# interface.net
KiCad netlist of a schematic drawn in Altium Designer
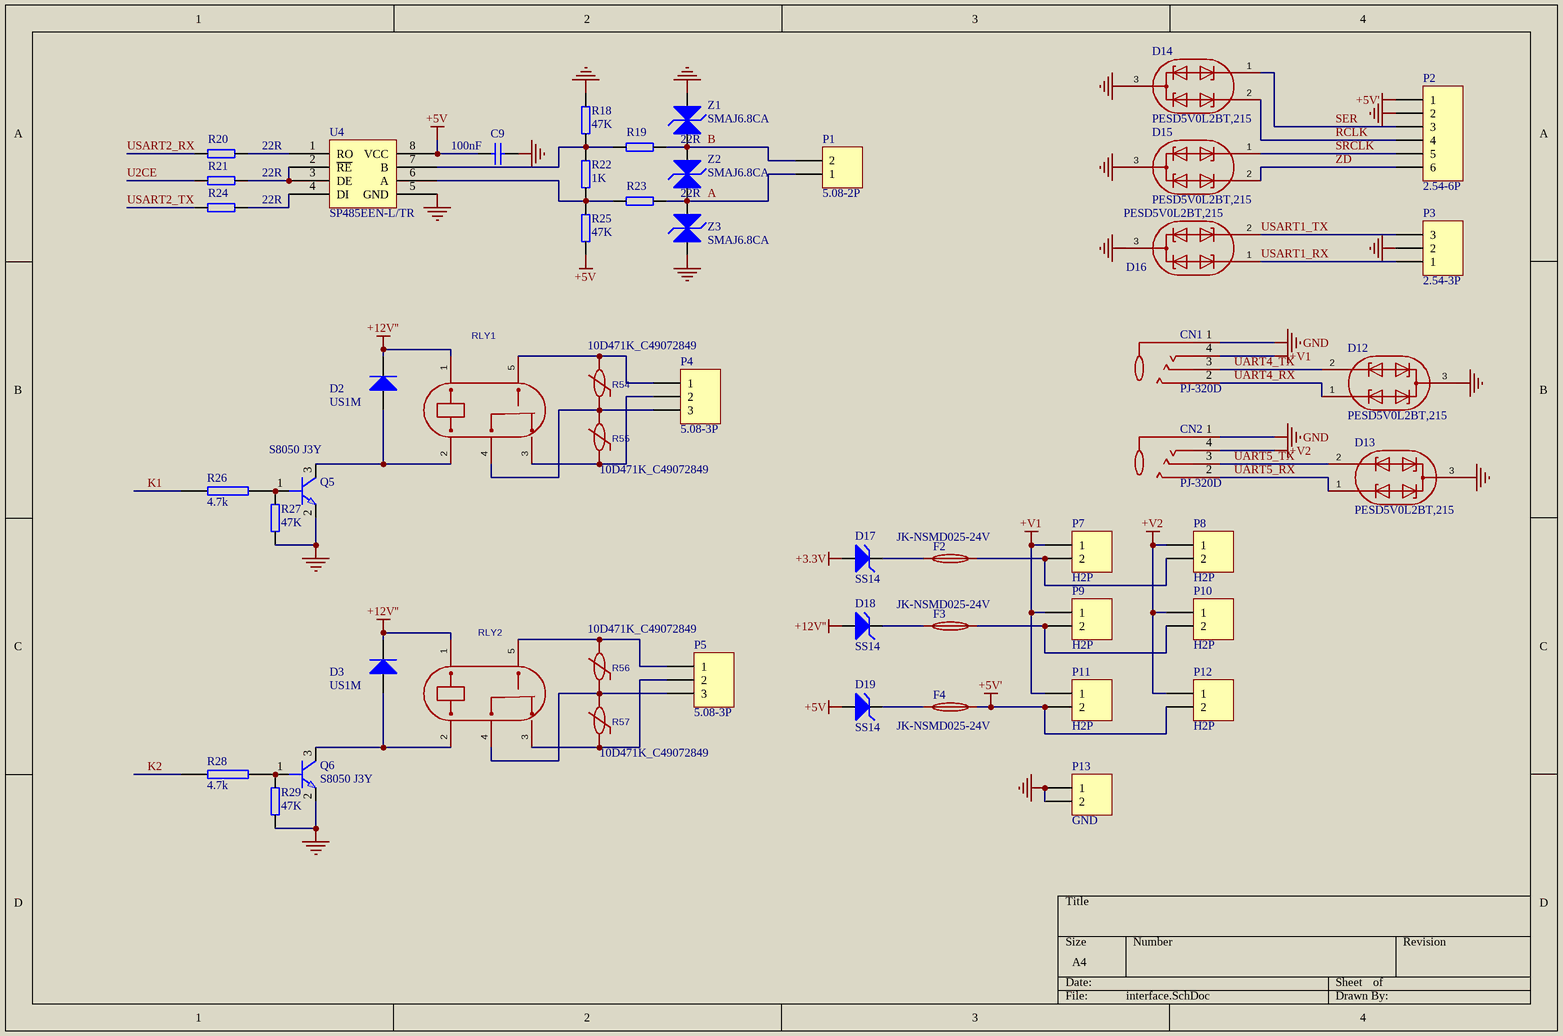
[diagram p0: interface.SchDoc]

(export (version "E")
  (design (tool "Eeschema 10.0.6"))
  (components
    (comp (ref "C9")
      (value "100nF")
      (footprint "LC-0805_C")
      (description "Capacitor")
      (fields (field (name "PUBLISHER") "Altium Limited"))
      (libsource (lib "*") (part "CAP"))
    )
    (comp (ref "CN1")
      (value "PJ-320D")
      (footprint "4PIN")
      (fields (field (name "MANUFACTURER") "SHOU HAN(首韩)"))
      (libsource (lib "altium-import") (part "root_0_PJ-320D_C431535_"))
    )
    (comp (ref "CN2")
      (value "PJ-320D")
      (footprint "4PIN")
      (fields (field (name "MANUFACTURER") "SHOU HAN(首韩)"))
      (libsource (lib "altium-import") (part "root_0_PJ-320D_C431535_"))
    )
    (comp (ref "D2")
      (value "US1M")
      (footprint "LC-SMA(DO-214AC)_S2")
      (description "Default Diode")
      (fields (field (name "PUBLISHER") "Altium Limited"))
      (libsource (lib "Miscellaneous Devices") (part "Diode"))
    )
    (comp (ref "D3")
      (value "US1M")
      (footprint "LC-SMA(DO-214AC)_S2")
      (description "Default Diode")
      (fields (field (name "PUBLISHER") "Altium Limited"))
      (libsource (lib "Miscellaneous Devices") (part "Diode"))
    )
    (comp (ref "D12")
      (value "PESD5V0L2BT,215")
      (footprint "SOT-23")
      (libsource (lib "altium-import") (part "root_2_mirrored_PESD5V0L2BT,215_"))
    )
    (comp (ref "D13")
      (value "PESD5V0L2BT,215")
      (footprint "SOT-23")
      (libsource (lib "altium-import") (part "root_2_mirrored_PESD5V0L2BT,215_"))
    )
    (comp (ref "D14")
      (value "PESD5V0L2BT,215")
      (footprint "SOT-23")
      (libsource (lib "altium-import") (part "root_0_mirrored_PESD5V0L2BT,215_"))
    )
    (comp (ref "D15")
      (value "PESD5V0L2BT,215")
      (footprint "SOT-23")
      (libsource (lib "altium-import") (part "root_0_mirrored_PESD5V0L2BT,215_"))
    )
    (comp (ref "D16")
      (value "PESD5V0L2BT,215")
      (footprint "SOT-23")
      (libsource (lib "altium-import") (part "root_2_PESD5V0L2BT,215_"))
    )
    (comp (ref "D17")
      (value "SS14")
      (footprint "LC-SMA(DO-214AC)_S5")
      (description "constant diode")
      (libsource (lib "*") (part "CONSTANT"))
    )
    (comp (ref "D18")
      (value "SS14")
      (footprint "LC-SMA(DO-214AC)_S5")
      (description "constant diode")
      (libsource (lib "*") (part "CONSTANT"))
    )
    (comp (ref "D19")
      (value "SS14")
      (footprint "LC-SMA(DO-214AC)_S5")
      (description "constant diode")
      (libsource (lib "*") (part "CONSTANT"))
    )
    (comp (ref "F2")
      (value "JK-NSMD025-24V")
      (footprint "LC-1206_R")
      (fields (field (name "MANUFACTURER") "JK(金科)") (field (name "MANUFACTURER PART") "JK-MSMD110-24V"))
      (libsource (lib "altium-import") (part "root_0_JK-MSMD110-24V_"))
    )
    (comp (ref "F3")
      (value "JK-NSMD025-24V")
      (footprint "LC-1206_R")
      (fields (field (name "MANUFACTURER") "JK(金科)") (field (name "MANUFACTURER PART") "JK-MSMD110-24V"))
      (libsource (lib "altium-import") (part "root_0_JK-MSMD110-24V_"))
    )
    (comp (ref "F4")
      (value "JK-NSMD025-24V")
      (footprint "LC-1206_R")
      (fields (field (name "MANUFACTURER") "JK(金科)") (field (name "MANUFACTURER PART") "JK-MSMD110-24V"))
      (libsource (lib "altium-import") (part "root_0_JK-MSMD110-24V_"))
    )
    (comp (ref "P1")
      (value "5.08-2P")
      (footprint "MKDSN_2RMI")
      (description "Header, 2-Pin")
      (fields (field (name "PUBLISHER") "Altium Limited"))
      (libsource (lib "") (part "Header 2_1"))
    )
    (comp (ref "P2")
      (value "2.54-6P")
      (footprint "6PIN")
      (description "Header, 6-Pin")
      (fields (field (name "PUBLISHER") "Altium Limited"))
      (libsource (lib "Miscellaneous Connectors") (part "Header 6"))
    )
    (comp (ref "P3")
      (value "2.54-3P")
      (footprint "3PIN")
      (description "Header, 3-Pin")
      (fields (field (name "PUBLISHER") "Altium Limited"))
      (libsource (lib "") (part "Header 3_1"))
    )
    (comp (ref "P4")
      (value "5.08-3P")
      (footprint "5.08-3P")
      (description "Header, 3-Pin")
      (fields (field (name "PUBLISHER") "Altium Limited"))
      (libsource (lib "Miscellaneous Connectors") (part "Header 3"))
    )
    (comp (ref "P5")
      (value "5.08-3P")
      (footprint "5.08-3P")
      (description "Header, 3-Pin")
      (fields (field (name "PUBLISHER") "Altium Limited"))
      (libsource (lib "Miscellaneous Connectors") (part "Header 3"))
    )
    (comp (ref "P7")
      (value "H2P")
      (footprint "HDR1X2")
      (description "Header, 2-Pin")
      (fields (field (name "PUBLISHER") "Altium Limited"))
      (libsource (lib "Miscellaneous Connectors") (part "Header 2"))
    )
    (comp (ref "P8")
      (value "H2P")
      (footprint "HDR1X2")
      (description "Header, 2-Pin")
      (fields (field (name "PUBLISHER") "Altium Limited"))
      (libsource (lib "Miscellaneous Connectors") (part "Header 2"))
    )
    (comp (ref "P9")
      (value "H2P")
      (footprint "HDR1X2")
      (description "Header, 2-Pin")
      (fields (field (name "PUBLISHER") "Altium Limited"))
      (libsource (lib "Miscellaneous Connectors") (part "Header 2"))
    )
    (comp (ref "P10")
      (value "H2P")
      (footprint "HDR1X2")
      (description "Header, 2-Pin")
      (fields (field (name "PUBLISHER") "Altium Limited"))
      (libsource (lib "Miscellaneous Connectors") (part "Header 2"))
    )
    (comp (ref "P11")
      (value "H2P")
      (footprint "HDR1X2")
      (description "Header, 2-Pin")
      (fields (field (name "PUBLISHER") "Altium Limited"))
      (libsource (lib "Miscellaneous Connectors") (part "Header 2"))
    )
    (comp (ref "P12")
      (value "H2P")
      (footprint "HDR1X2")
      (description "Header, 2-Pin")
      (fields (field (name "PUBLISHER") "Altium Limited"))
      (libsource (lib "Miscellaneous Connectors") (part "Header 2"))
    )
    (comp (ref "P13")
      (value "GND")
      (footprint "HDR1X2")
      (description "Header, 2-Pin")
      (fields (field (name "PUBLISHER") "Altium Limited"))
      (libsource (lib "Miscellaneous Connectors") (part "Header 2"))
    )
    (comp (ref "Q5") (value "S8050 J3Y") (footprint "SOT-23") (libsource (lib "*") (part "2N5551")))
    (comp (ref "Q6") (value "S8050 J3Y") (footprint "SOT-23") (libsource (lib "*") (part "2N5551")))
    (comp (ref "R18")
      (value "47K")
      (footprint "LC-0805_R")
      (description "1K")
      (libsource (lib "*") (part "RES22"))
    )
    (comp (ref "R19") (value "22R") (footprint "LC-0805_R") (libsource (lib "*") (part "RES22")))
    (comp (ref "R20")
      (value "22R")
      (footprint "LC-0805_R")
      (description "1K")
      (libsource (lib "*") (part "RES22"))
    )
    (comp (ref "R21")
      (value "22R")
      (footprint "LC-0805_R")
      (description "1K")
      (libsource (lib "*") (part "RES22"))
    )
    (comp (ref "R22") (value "1K") (footprint "LC-0805_R") (libsource (lib "*") (part "RES22")))
    (comp (ref "R23")
      (value "22R")
      (footprint "LC-0805_R")
      (description "1K")
      (libsource (lib "*") (part "RES22"))
    )
    (comp (ref "R24")
      (value "22R")
      (footprint "LC-0805_R")
      (description "1K")
      (libsource (lib "*") (part "RES22"))
    )
    (comp (ref "R25")
      (value "47K")
      (footprint "LC-0805_R")
      (description "1K")
      (libsource (lib "*") (part "RES22"))
    )
    (comp (ref "R26") (value "4.7k") (footprint "LC-0805_R") (libsource (lib "*") (part "RES2")))
    (comp (ref "R27")
      (value "47K")
      (footprint "LC-0805_R")
      (description "1K")
      (libsource (lib "*") (part "RES22"))
    )
    (comp (ref "R28") (value "4.7k") (footprint "LC-0805_R") (libsource (lib "*") (part "RES2")))
    (comp (ref "R29")
      (value "47K")
      (footprint "LC-0805_R")
      (description "1K")
      (libsource (lib "*") (part "RES22"))
    )
    (comp (ref "R54")
      (value "10D471K_C49072849")
      (footprint "RES-TH_L11.0-W6.0-P7.50")
      (libsource (lib "altium-import") (part "root_1_14D471K_C49069733_"))
    )
    (comp (ref "R55")
      (value "10D471K_C49072849")
      (footprint "RES-TH_L11.0-W6.0-P7.50")
      (libsource (lib "altium-import") (part "root_1_14D471K_C49069733_"))
    )
    (comp (ref "R56")
      (value "10D471K_C49072849")
      (footprint "RES-TH_L11.0-W6.0-P7.50")
      (libsource (lib "altium-import") (part "root_1_14D471K_C49069733_"))
    )
    (comp (ref "R57")
      (value "10D471K_C49072849")
      (footprint "RES-TH_L11.0-W6.0-P7.50")
      (libsource (lib "altium-import") (part "root_1_14D471K_C49069733_"))
    )
    (comp (ref "RLY1")
      (value "JQC-3FF/12VDC-1ZS(551)")
      (libsource (lib "altium-import") (part "root_0_JQC-3FF/12VDC-1ZS(551)_"))
    )
    (comp (ref "RLY2")
      (value "JQC-3FF/12VDC-1ZS(551)")
      (libsource (lib "altium-import") (part "root_0_JQC-3FF/12VDC-1ZS(551)_"))
    )
    (comp (ref "U4")
      (value "SP485EEN-L/TR")
      (footprint "LC-SOIC-8_150mil")
      (libsource (lib "*") (part "MAX483"))
    )
    (comp (ref "Z1")
      (value "SMAJ6.8CA")
      (footprint "1812")
      (description "DIODE BRIDGE")
      (libsource (lib "*") (part "BANQIAO"))
    )
    (comp (ref "Z2")
      (value "SMAJ6.8CA")
      (footprint "1812")
      (description "DIODE BRIDGE")
      (libsource (lib "*") (part "BANQIAO"))
    )
    (comp (ref "Z3")
      (value "SMAJ6.8CA")
      (footprint "1812")
      (description "DIODE BRIDGE")
      (libsource (lib "*") (part "BANQIAO"))
    )
  )
  (nets
    (net (code "1") (name "+3.3V") (class "Default")
      (node (ref "D17") (pin "1") (pinfunction "A_1") (pintype "passive"))
    )
    (net (code "2") (name "+5V") (class "Default")
      (node (ref "C9") (pin "2") (pinfunction "2_2") (pintype "passive"))
      (node (ref "D19") (pin "1") (pinfunction "A_1") (pintype "passive"))
      (node (ref "R25") (pin "1") (pintype "passive"))
      (node (ref "U4") (pin "8") (pinfunction "VCC_8") (pintype "passive"))
    )
    (net (code "3") (name "+5V'") (class "Default")
      (node (ref "F4") (pin "2") (pinfunction "2_2") (pintype "passive"))
      (node (ref "P11") (pin "2") (pinfunction "2_2") (pintype "passive"))
      (node (ref "P12") (pin "2") (pinfunction "2_2") (pintype "passive"))
      (node (ref "P2") (pin "1") (pinfunction "1_1") (pintype "passive"))
    )
    (net (code "4") (name "+12V''") (class "Default")
      (node (ref "D18") (pin "1") (pinfunction "A_1") (pintype "passive"))
      (node (ref "D2") (pin "2") (pinfunction "K_2") (pintype "passive"))
      (node (ref "D3") (pin "2") (pinfunction "K_2") (pintype "passive"))
      (node (ref "RLY1") (pin "1") (pinfunction "1_1") (pintype "passive"))
      (node (ref "RLY2") (pin "1") (pinfunction "1_1") (pintype "passive"))
    )
    (net (code "5") (name "+V1") (class "Default")
      (node (ref "CN1") (pin "4") (pinfunction "4_4") (pintype "passive"))
      (node (ref "P11") (pin "1") (pinfunction "1_1") (pintype "passive"))
      (node (ref "P7") (pin "1") (pinfunction "1_1") (pintype "passive"))
      (node (ref "P9") (pin "1") (pinfunction "1_1") (pintype "passive"))
    )
    (net (code "6") (name "+V2") (class "Default")
      (node (ref "CN2") (pin "4") (pinfunction "4_4") (pintype "passive"))
      (node (ref "P10") (pin "1") (pinfunction "1_1") (pintype "passive"))
      (node (ref "P12") (pin "1") (pinfunction "1_1") (pintype "passive"))
      (node (ref "P8") (pin "1") (pinfunction "1_1") (pintype "passive"))
    )
    (net (code "7") (name "/A") (class "Default")
      (node (ref "P1") (pin "1") (pinfunction "1_1") (pintype "passive"))
      (node (ref "R23") (pin "2") (pintype "passive"))
      (node (ref "Z2") (pin "2") (pinfunction "2_2") (pintype "passive"))
      (node (ref "Z3") (pin "1") (pinfunction "1_1") (pintype "passive"))
    )
    (net (code "8") (name "/B") (class "Default")
      (node (ref "P1") (pin "2") (pinfunction "2_2") (pintype "passive"))
      (node (ref "R19") (pin "2") (pintype "passive"))
      (node (ref "Z1") (pin "2") (pinfunction "2_2") (pintype "passive"))
      (node (ref "Z2") (pin "1") (pinfunction "1_1") (pintype "passive"))
    )
    (net (code "9") (name "/K1") (class "Default")
      (node (ref "R26") (pin "1") (pinfunction "1_1") (pintype "passive"))
    )
    (net (code "10") (name "/K2") (class "Default")
      (node (ref "R28") (pin "1") (pinfunction "1_1") (pintype "passive"))
    )
    (net (code "11") (name "/RCLK") (class "Default")
      (node (ref "D14") (pin "2") (pinfunction "C2_2") (pintype "passive"))
      (node (ref "P2") (pin "4") (pinfunction "4_4") (pintype "passive"))
    )
    (net (code "12") (name "/SER") (class "Default")
      (node (ref "D14") (pin "1") (pinfunction "C1_1") (pintype "passive"))
      (node (ref "P2") (pin "3") (pinfunction "3_3") (pintype "passive"))
    )
    (net (code "13") (name "/SRCLK") (class "Default")
      (node (ref "D15") (pin "1") (pinfunction "C1_1") (pintype "passive"))
      (node (ref "P2") (pin "5") (pinfunction "5_5") (pintype "passive"))
    )
    (net (code "14") (name "/U2CE") (class "Default") (node (ref "R21") (pin "1") (pintype "passive")))
    (net (code "15") (name "/UART4_RX") (class "Default")
      (node (ref "CN1") (pin "2") (pinfunction "2_2") (pintype "passive"))
      (node (ref "D12") (pin "1") (pinfunction "C1_1") (pintype "passive"))
    )
    (net (code "16") (name "/UART4_TX") (class "Default")
      (node (ref "CN1") (pin "3") (pinfunction "3_3") (pintype "passive"))
      (node (ref "D12") (pin "2") (pinfunction "C2_2") (pintype "passive"))
    )
    (net (code "17") (name "/UART5_RX") (class "Default")
      (node (ref "CN2") (pin "2") (pinfunction "2_2") (pintype "passive"))
      (node (ref "D13") (pin "1") (pinfunction "C1_1") (pintype "passive"))
    )
    (net (code "18") (name "/UART5_TX") (class "Default")
      (node (ref "CN2") (pin "3") (pinfunction "3_3") (pintype "passive"))
      (node (ref "D13") (pin "2") (pinfunction "C2_2") (pintype "passive"))
    )
    (net (code "19") (name "/USART1_RX") (class "Default")
      (node (ref "D16") (pin "1") (pinfunction "C1_1") (pintype "passive"))
      (node (ref "P3") (pin "1") (pinfunction "1_1") (pintype "passive"))
    )
    (net (code "20") (name "/USART1_TX") (class "Default")
      (node (ref "D16") (pin "2") (pinfunction "C2_2") (pintype "passive"))
      (node (ref "P3") (pin "3") (pinfunction "3_3") (pintype "passive"))
    )
    (net (code "21") (name "/USART2_RX") (class "Default") (node (ref "R20") (pin "1") (pintype "passive")))
    (net (code "22") (name "/USART2_TX") (class "Default") (node (ref "R24") (pin "1") (pintype "passive")))
    (net (code "23") (name "/ZD") (class "Default")
      (node (ref "D15") (pin "2") (pinfunction "C2_2") (pintype "passive"))
      (node (ref "P2") (pin "6") (pinfunction "6_6") (pintype "passive"))
    )
    (net (code "24") (name "GND") (class "Default")
      (node (ref "C9") (pin "1") (pinfunction "1_1") (pintype "passive"))
      (node (ref "CN1") (pin "1") (pinfunction "1_1") (pintype "passive"))
      (node (ref "CN2") (pin "1") (pinfunction "1_1") (pintype "passive"))
      (node (ref "D12") (pin "3") (pinfunction "DC_3") (pintype "passive"))
      (node (ref "D13") (pin "3") (pinfunction "DC_3") (pintype "passive"))
      (node (ref "D14") (pin "3") (pinfunction "DC_3") (pintype "passive"))
      (node (ref "D15") (pin "3") (pinfunction "DC_3") (pintype "passive"))
      (node (ref "D16") (pin "3") (pinfunction "DC_3") (pintype "passive"))
      (node (ref "P13") (pin "1") (pinfunction "1_1") (pintype "passive"))
      (node (ref "P13") (pin "2") (pinfunction "2_2") (pintype "passive"))
      (node (ref "P2") (pin "2") (pinfunction "2_2") (pintype "passive"))
      (node (ref "P3") (pin "2") (pinfunction "2_2") (pintype "passive"))
      (node (ref "Q5") (pin "2") (pinfunction "E_2") (pintype "passive"))
      (node (ref "Q6") (pin "2") (pinfunction "E_2") (pintype "passive"))
      (node (ref "R18") (pin "2") (pintype "passive"))
      (node (ref "R27") (pin "1") (pintype "passive"))
      (node (ref "R29") (pin "1") (pintype "passive"))
      (node (ref "U4") (pin "5") (pinfunction "GND_5") (pintype "passive"))
      (node (ref "Z1") (pin "1") (pinfunction "1_1") (pintype "passive"))
      (node (ref "Z3") (pin "2") (pinfunction "2_2") (pintype "passive"))
    )
    (net (code "25") (name "Net-(D2-A)") (class "Default")
      (node (ref "D2") (pin "1") (pinfunction "A_1") (pintype "passive"))
      (node (ref "Q5") (pin "3") (pinfunction "C_3") (pintype "passive"))
      (node (ref "RLY1") (pin "2") (pinfunction "2_2") (pintype "passive"))
    )
    (net (code "26") (name "Net-(D3-A)") (class "Default")
      (node (ref "D3") (pin "1") (pinfunction "A_1") (pintype "passive"))
      (node (ref "Q6") (pin "3") (pinfunction "C_3") (pintype "passive"))
      (node (ref "RLY2") (pin "2") (pinfunction "2_2") (pintype "passive"))
    )
    (net (code "27") (name "Net-(D17-K)") (class "Default")
      (node (ref "D17") (pin "2") (pinfunction "K_2") (pintype "passive"))
      (node (ref "F2") (pin "1") (pinfunction "1_1") (pintype "passive"))
    )
    (net (code "28") (name "Net-(D18-K)") (class "Default")
      (node (ref "D18") (pin "2") (pinfunction "K_2") (pintype "passive"))
      (node (ref "F3") (pin "1") (pinfunction "1_1") (pintype "passive"))
    )
    (net (code "29") (name "Net-(D19-K)") (class "Default")
      (node (ref "D19") (pin "2") (pinfunction "K_2") (pintype "passive"))
      (node (ref "F4") (pin "1") (pinfunction "1_1") (pintype "passive"))
    )
    (net (code "30") (name "Net-(F2-Pad2)") (class "Default")
      (node (ref "F2") (pin "2") (pinfunction "2_2") (pintype "passive"))
      (node (ref "P7") (pin "2") (pinfunction "2_2") (pintype "passive"))
      (node (ref "P8") (pin "2") (pinfunction "2_2") (pintype "passive"))
    )
    (net (code "31") (name "Net-(F3-Pad2)") (class "Default")
      (node (ref "F3") (pin "2") (pinfunction "2_2") (pintype "passive"))
      (node (ref "P10") (pin "2") (pinfunction "2_2") (pintype "passive"))
      (node (ref "P9") (pin "2") (pinfunction "2_2") (pintype "passive"))
    )
    (net (code "32") (name "Net-(P4-Pad1)") (class "Default")
      (node (ref "P4") (pin "1") (pinfunction "1_1") (pintype "passive"))
      (node (ref "R54") (pin "2") (pinfunction "2_2") (pintype "passive"))
      (node (ref "RLY1") (pin "5") (pinfunction "5_5") (pintype "passive"))
    )
    (net (code "33") (name "Net-(P4-Pad2)") (class "Default")
      (node (ref "P4") (pin "2") (pinfunction "2_2") (pintype "passive"))
      (node (ref "R55") (pin "1") (pinfunction "1_1") (pintype "passive"))
      (node (ref "RLY1") (pin "3") (pinfunction "3_3") (pintype "passive"))
    )
    (net (code "34") (name "Net-(P4-Pad3)") (class "Default")
      (node (ref "P4") (pin "3") (pinfunction "3_3") (pintype "passive"))
      (node (ref "R54") (pin "1") (pinfunction "1_1") (pintype "passive"))
      (node (ref "R55") (pin "2") (pinfunction "2_2") (pintype "passive"))
      (node (ref "RLY1") (pin "4") (pinfunction "4_4") (pintype "passive"))
    )
    (net (code "35") (name "Net-(P5-Pad1)") (class "Default")
      (node (ref "P5") (pin "1") (pinfunction "1_1") (pintype "passive"))
      (node (ref "R56") (pin "2") (pinfunction "2_2") (pintype "passive"))
      (node (ref "RLY2") (pin "5") (pinfunction "5_5") (pintype "passive"))
    )
    (net (code "36") (name "Net-(P5-Pad2)") (class "Default")
      (node (ref "P5") (pin "2") (pinfunction "2_2") (pintype "passive"))
      (node (ref "R57") (pin "1") (pinfunction "1_1") (pintype "passive"))
      (node (ref "RLY2") (pin "3") (pinfunction "3_3") (pintype "passive"))
    )
    (net (code "37") (name "Net-(P5-Pad3)") (class "Default")
      (node (ref "P5") (pin "3") (pinfunction "3_3") (pintype "passive"))
      (node (ref "R56") (pin "1") (pinfunction "1_1") (pintype "passive"))
      (node (ref "R57") (pin "2") (pinfunction "2_2") (pintype "passive"))
      (node (ref "RLY2") (pin "4") (pinfunction "4_4") (pintype "passive"))
    )
    (net (code "38") (name "Net-(Q5-B)") (class "Default")
      (node (ref "Q5") (pin "1") (pinfunction "B_1") (pintype "passive"))
      (node (ref "R26") (pin "2") (pinfunction "2_2") (pintype "passive"))
      (node (ref "R27") (pin "2") (pintype "passive"))
    )
    (net (code "39") (name "Net-(Q6-B)") (class "Default")
      (node (ref "Q6") (pin "1") (pinfunction "B_1") (pintype "passive"))
      (node (ref "R28") (pin "2") (pinfunction "2_2") (pintype "passive"))
      (node (ref "R29") (pin "2") (pintype "passive"))
    )
    (net (code "40") (name "Net-(U4-A)") (class "Default")
      (node (ref "R22") (pin "1") (pintype "passive"))
      (node (ref "R23") (pin "1") (pintype "passive"))
      (node (ref "R25") (pin "2") (pintype "passive"))
      (node (ref "U4") (pin "6") (pinfunction "A_6") (pintype "passive"))
    )
    (net (code "41") (name "Net-(U4-B)") (class "Default")
      (node (ref "R18") (pin "1") (pintype "passive"))
      (node (ref "R19") (pin "1") (pintype "passive"))
      (node (ref "R22") (pin "2") (pintype "passive"))
      (node (ref "U4") (pin "7") (pinfunction "B_7") (pintype "passive"))
    )
    (net (code "42") (name "Net-(U4-DE)") (class "Default")
      (node (ref "R21") (pin "2") (pintype "passive"))
      (node (ref "U4") (pin "2") (pinfunction "~{RE}_2") (pintype "passive"))
      (node (ref "U4") (pin "3") (pinfunction "DE_3") (pintype "passive"))
    )
    (net (code "43") (name "Net-(U4-DI)") (class "Default")
      (node (ref "R24") (pin "2") (pintype "passive"))
      (node (ref "U4") (pin "4") (pinfunction "DI_4") (pintype "passive"))
    )
    (net (code "44") (name "Net-(U4-RO)") (class "Default")
      (node (ref "R20") (pin "2") (pintype "passive"))
      (node (ref "U4") (pin "1") (pinfunction "RO_1") (pintype "passive"))
    )
  )
)
